# Filter.net
KiCad netlist of a schematic drawn in Altium Designer
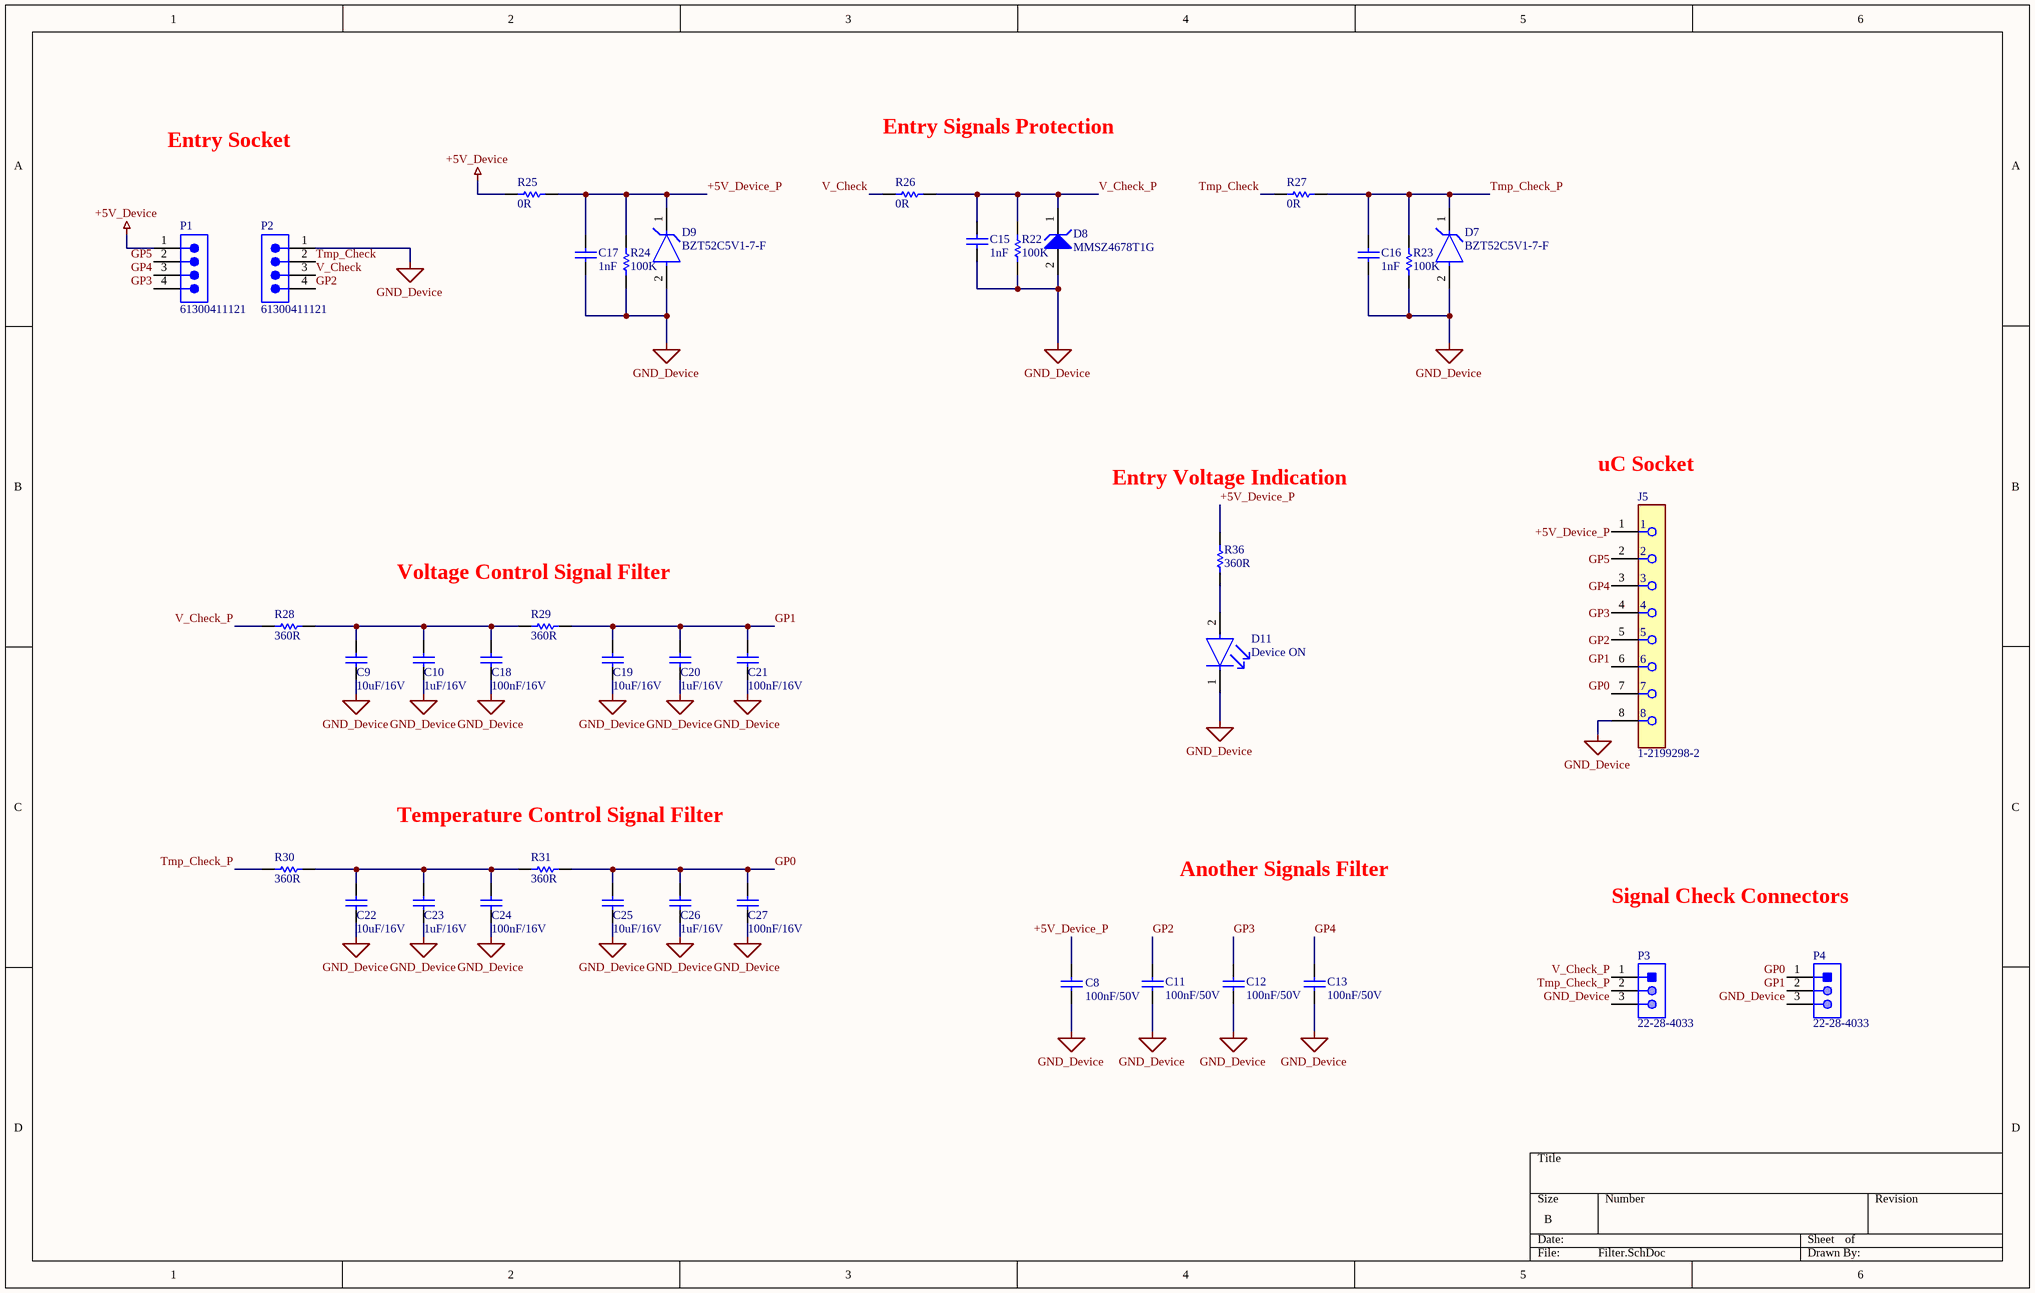
[diagram p0: Filter.SchDoc]

(export (version "E")
  (design (tool "Eeschema 10.0.6"))
  (components
    (comp (ref "C8")
      (value "100nF/50V")
      (footprint "CAPC2013X145X48NL20T23")
      (fields (field (name "MANUFACTURER") "Vitramon") (field (name "PART NUMBER") "VJ0805Y104KNAAT"))
      (libsource (lib "Altium Content Vault") (part "CAP"))
    )
    (comp (ref "C9")
      (value "10uF/16V")
      (footprint "CAPC2013X145X48NL20T23")
      (fields (field (name "MANUFACTURER") "Vitramon") (field (name "PART NUMBER") "VJ0805Y104KNAAT"))
      (libsource (lib "Altium Content Vault") (part "CAP"))
    )
    (comp (ref "C10")
      (value "1uF/16V")
      (footprint "CAPC2013X145X48NL20T23")
      (fields (field (name "MANUFACTURER") "Vitramon") (field (name "PART NUMBER") "VJ0805Y104KNAAT"))
      (libsource (lib "Altium Content Vault") (part "CAP"))
    )
    (comp (ref "C11")
      (value "100nF/50V")
      (footprint "CAPC2013X145X48NL20T23")
      (fields (field (name "MANUFACTURER") "Vitramon") (field (name "PART NUMBER") "VJ0805Y104KNAAT"))
      (libsource (lib "Altium Content Vault") (part "CAP"))
    )
    (comp (ref "C12")
      (value "100nF/50V")
      (footprint "CAPC2013X145X48NL20T23")
      (fields (field (name "MANUFACTURER") "Vitramon") (field (name "PART NUMBER") "VJ0805Y104KNAAT"))
      (libsource (lib "Altium Content Vault") (part "CAP"))
    )
    (comp (ref "C13")
      (value "100nF/50V")
      (footprint "CAPC2013X145X48NL20T23")
      (fields (field (name "MANUFACTURER") "Vitramon") (field (name "PART NUMBER") "VJ0805Y104KNAAT"))
      (libsource (lib "Altium Content Vault") (part "CAP"))
    )
    (comp (ref "C15")
      (value "1nF")
      (footprint "CAPC2013X145X48ML20T23")
      (fields (field (name "PART NUMBER") "VJ0805Y102KXAMC") (field (name "MANUFACTURER") "Vitramon"))
      (libsource (lib "Altium Content Vault") (part "CAP"))
    )
    (comp (ref "C16")
      (value "1nF")
      (footprint "CAPC2013X145X48ML20T23")
      (fields (field (name "PART NUMBER") "VJ0805Y102KXAMC") (field (name "MANUFACTURER") "Vitramon"))
      (libsource (lib "Altium Content Vault") (part "CAP"))
    )
    (comp (ref "C17")
      (value "1nF")
      (footprint "CAPC2013X145X48ML20T23")
      (fields (field (name "PART NUMBER") "VJ0805Y102KXAMC") (field (name "MANUFACTURER") "Vitramon"))
      (libsource (lib "Altium Content Vault") (part "CAP"))
    )
    (comp (ref "C18")
      (value "100nF/16V")
      (footprint "CAPC2013X145X48NL20T23")
      (fields (field (name "MANUFACTURER") "Vitramon") (field (name "PART NUMBER") "VJ0805Y104KNAAT"))
      (libsource (lib "Altium Content Vault") (part "CAP"))
    )
    (comp (ref "C19")
      (value "10uF/16V")
      (footprint "CAPC2013X145X48NL20T23")
      (fields (field (name "MANUFACTURER") "Vitramon") (field (name "PART NUMBER") "VJ0805Y104KNAAT"))
      (libsource (lib "Altium Content Vault") (part "CAP"))
    )
    (comp (ref "C20")
      (value "1uF/16V")
      (footprint "CAPC2013X145X48NL20T23")
      (fields (field (name "MANUFACTURER") "Vitramon") (field (name "PART NUMBER") "VJ0805Y104KNAAT"))
      (libsource (lib "Altium Content Vault") (part "CAP"))
    )
    (comp (ref "C21")
      (value "100nF/16V")
      (footprint "CAPC2013X145X48NL20T23")
      (fields (field (name "MANUFACTURER") "Vitramon") (field (name "PART NUMBER") "VJ0805Y104KNAAT"))
      (libsource (lib "Altium Content Vault") (part "CAP"))
    )
    (comp (ref "C22")
      (value "10uF/16V")
      (footprint "CAPC2013X145X48NL20T23")
      (fields (field (name "MANUFACTURER") "Vitramon") (field (name "PART NUMBER") "VJ0805Y104KNAAT"))
      (libsource (lib "Altium Content Vault") (part "CAP"))
    )
    (comp (ref "C23")
      (value "1uF/16V")
      (footprint "CAPC2013X145X48NL20T23")
      (fields (field (name "MANUFACTURER") "Vitramon") (field (name "PART NUMBER") "VJ0805Y104KNAAT"))
      (libsource (lib "Altium Content Vault") (part "CAP"))
    )
    (comp (ref "C24")
      (value "100nF/16V")
      (footprint "CAPC2013X145X48NL20T23")
      (fields (field (name "MANUFACTURER") "Vitramon") (field (name "PART NUMBER") "VJ0805Y104KNAAT"))
      (libsource (lib "Altium Content Vault") (part "CAP"))
    )
    (comp (ref "C25")
      (value "10uF/16V")
      (footprint "CAPC2013X145X48NL20T23")
      (fields (field (name "MANUFACTURER") "Vitramon") (field (name "PART NUMBER") "VJ0805Y104KNAAT"))
      (libsource (lib "Altium Content Vault") (part "CAP"))
    )
    (comp (ref "C26")
      (value "1uF/16V")
      (footprint "CAPC2013X145X48NL20T23")
      (fields (field (name "MANUFACTURER") "Vitramon") (field (name "PART NUMBER") "VJ0805Y104KNAAT"))
      (libsource (lib "Altium Content Vault") (part "CAP"))
    )
    (comp (ref "C27")
      (value "100nF/16V")
      (footprint "CAPC2013X145X48NL20T23")
      (fields (field (name "MANUFACTURER") "Vitramon") (field (name "PART NUMBER") "VJ0805Y104KNAAT"))
      (libsource (lib "Altium Content Vault") (part "CAP"))
    )
    (comp (ref "D7")
      (value "BZT52C5V1-7-F")
      (footprint "FP-SOD123-MFG")
      (description "DIODE ZENER 5.1V 500MW SOD123")
      (fields
        (field (name "OCTOPART") "https://octopart.com/bzt52c5v1-7-f-diodes+inc.-326718")
        (field (name "MANUFACTURER") "Diodes Incorporated")
      )
      (libsource (lib "Altium Content Vault") (part "f813f71cba58e380607f5dd3caf9714"))
    )
    (comp (ref "D8")
      (value "MMSZ4678T1G")
      (footprint "ONSC-SOD-123-2-425-04_V")
      (description "Zener Voltage Regulator, 500 mW, 2-Pin SOD-123, Pb-Free, Tape and Reel")
      (fields (field (name "MANUFACTURER") "On Semiconductor"))
      (libsource (lib "Altium Content Vault") (part "ONSC-K1A2-2"))
    )
    (comp (ref "D9")
      (value "BZT52C5V1-7-F")
      (footprint "FP-SOD123-MFG")
      (description "DIODE ZENER 5.1V 500MW SOD123")
      (fields
        (field (name "OCTOPART") "https://octopart.com/bzt52c5v1-7-f-diodes+inc.-326718")
        (field (name "MANUFACTURER") "Diodes Incorporated")
      )
      (libsource (lib "Altium Content Vault") (part "f813f71cba58e380607f5dd3caf9714"))
    )
    (comp (ref "D11")
      (value "Device ON")
      (footprint "FP-LS_R976-MFG")
      (description "LED RED DIFFUSED 0805 SMD")
      (libsource (lib "Altium Content Vault") (part "8706943c75ba83719d021d2fdc84c58"))
    )
    (comp (ref "J5")
      (value "1-2199298-2")
      (footprint "FP-1-2199298-2-MFG")
      (description "CONN IC DIP SOCKET 8POS TIN")
      (libsource (lib "Altium Content Vault") (part "b0a0b555dd3abf3683e7c330df25cc4"))
    )
    (comp (ref "P1")
      (value "61300411121")
      (footprint "61300411121")
      (libsource (lib "Altium Content Vault") (part "Header_Male_1R_04P"))
    )
    (comp (ref "P2")
      (value "61300411121")
      (footprint "61300411121")
      (libsource (lib "Altium Content Vault") (part "Header_Male_1R_04P"))
    )
    (comp (ref "P3")
      (value "22-28-4033")
      (footprint "MOLX-22-28-4033_V")
      (description "Male Header, Pitch 2.54 mm, 1 x 3 Position, Height 8.38 mm, Tail Length 3.18 mm, RoHS, Bulk")
      (fields (field (name "MANUFACTURER") "Molex"))
      (libsource (lib "Altium Content Vault") (part "CN-1P-M-R3"))
    )
    (comp (ref "P4")
      (value "22-28-4033")
      (footprint "MOLX-22-28-4033_V")
      (description "Male Header, Pitch 2.54 mm, 1 x 3 Position, Height 8.38 mm, Tail Length 3.18 mm, RoHS, Bulk")
      (fields (field (name "MANUFACTURER") "Molex"))
      (libsource (lib "Altium Content Vault") (part "CN-1P-M-R3"))
    )
    (comp (ref "R22")
      (value "100K")
      (footprint "RESC2013X55X40NL15T20")
      (fields (field (name "MANUFACTURER") "Vishay Dale") (field (name "PART NUMBER") "TNPW08052K00BEEN"))
      (libsource (lib "Altium Content Vault") (part "RES"))
    )
    (comp (ref "R23")
      (value "100K")
      (footprint "RESC2013X55X40NL15T20")
      (fields (field (name "MANUFACTURER") "Vishay Dale") (field (name "PART NUMBER") "TNPW08052K00BEEN"))
      (libsource (lib "Altium Content Vault") (part "RES"))
    )
    (comp (ref "R24")
      (value "100K")
      (footprint "RESC2013X55X40NL15T20")
      (fields (field (name "MANUFACTURER") "Vishay Dale") (field (name "PART NUMBER") "TNPW08052K00BEEN"))
      (libsource (lib "Altium Content Vault") (part "RES"))
    )
    (comp (ref "R25")
      (value "0R")
      (footprint "RESC2013X55X40NL15T20")
      (fields (field (name "MANUFACTURER") "Vishay Dale") (field (name "PART NUMBER") "TNPW08052K00BEEN"))
      (libsource (lib "Altium Content Vault") (part "RES"))
    )
    (comp (ref "R26")
      (value "0R")
      (footprint "RESC2013X55X40NL15T20")
      (fields (field (name "MANUFACTURER") "Vishay Dale") (field (name "PART NUMBER") "TNPW08052K00BEEN"))
      (libsource (lib "Altium Content Vault") (part "RES"))
    )
    (comp (ref "R27")
      (value "0R")
      (footprint "RESC2013X55X40NL15T20")
      (fields (field (name "MANUFACTURER") "Vishay Dale") (field (name "PART NUMBER") "TNPW08052K00BEEN"))
      (libsource (lib "Altium Content Vault") (part "RES"))
    )
    (comp (ref "R28")
      (value "360R")
      (footprint "RESC2013X55X40NL15T20")
      (fields (field (name "MANUFACTURER") "Vishay Dale") (field (name "PART NUMBER") "TNPW08052K00BEEN"))
      (libsource (lib "Altium Content Vault") (part "RES"))
    )
    (comp (ref "R29")
      (value "360R")
      (footprint "RESC2013X55X40NL15T20")
      (fields (field (name "MANUFACTURER") "Vishay Dale") (field (name "PART NUMBER") "TNPW08052K00BEEN"))
      (libsource (lib "Altium Content Vault") (part "RES"))
    )
    (comp (ref "R30")
      (value "360R")
      (footprint "RESC2013X55X40NL15T20")
      (fields (field (name "MANUFACTURER") "Vishay Dale") (field (name "PART NUMBER") "TNPW08052K00BEEN"))
      (libsource (lib "Altium Content Vault") (part "RES"))
    )
    (comp (ref "R31")
      (value "360R")
      (footprint "RESC2013X55X40NL15T20")
      (fields (field (name "MANUFACTURER") "Vishay Dale") (field (name "PART NUMBER") "TNPW08052K00BEEN"))
      (libsource (lib "Altium Content Vault") (part "RES"))
    )
    (comp (ref "R36")
      (value "360R")
      (footprint "RESC2013X55X40NL15T20")
      (fields (field (name "MANUFACTURER") "Vishay Dale") (field (name "PART NUMBER") "TNPW08052K00BEEN"))
      (libsource (lib "Altium Content Vault") (part "RES"))
    )
  )
  (nets
    (net (code "1") (name "+5V_Device") (class "Default")
      (node (ref "P1") (pin "1") (pinfunction "1_1") (pintype "passive"))
      (node (ref "R25") (pin "2") (pinfunction "2_2") (pintype "passive"))
    )
    (net (code "2") (name "/+5V_Device_P") (class "Default")
      (node (ref "C17") (pin "2") (pinfunction "2_2") (pintype "passive"))
      (node (ref "C8") (pin "2") (pinfunction "2_2") (pintype "passive"))
      (node (ref "D9") (pin "1") (pinfunction "C_1") (pintype "passive"))
      (node (ref "J5") (pin "1") (pinfunction "1_1") (pintype "passive"))
      (node (ref "R24") (pin "2") (pinfunction "2_2") (pintype "passive"))
      (node (ref "R25") (pin "1") (pinfunction "1_1") (pintype "passive"))
      (node (ref "R36") (pin "2") (pinfunction "2_2") (pintype "passive"))
    )
    (net (code "3") (name "/GP0") (class "Default")
      (node (ref "C25") (pin "2") (pinfunction "2_2") (pintype "passive"))
      (node (ref "C26") (pin "2") (pinfunction "2_2") (pintype "passive"))
      (node (ref "C27") (pin "2") (pinfunction "2_2") (pintype "passive"))
      (node (ref "J5") (pin "7") (pinfunction "7_7") (pintype "passive"))
      (node (ref "P4") (pin "1") (pinfunction "1_1") (pintype "passive"))
      (node (ref "R31") (pin "1") (pinfunction "1_1") (pintype "passive"))
    )
    (net (code "4") (name "/GP1") (class "Default")
      (node (ref "C19") (pin "2") (pinfunction "2_2") (pintype "passive"))
      (node (ref "C20") (pin "2") (pinfunction "2_2") (pintype "passive"))
      (node (ref "C21") (pin "2") (pinfunction "2_2") (pintype "passive"))
      (node (ref "J5") (pin "6") (pinfunction "6_6") (pintype "passive"))
      (node (ref "P4") (pin "2") (pinfunction "2_2") (pintype "passive"))
      (node (ref "R29") (pin "1") (pinfunction "1_1") (pintype "passive"))
    )
    (net (code "5") (name "/GP2") (class "Default")
      (node (ref "C11") (pin "1") (pinfunction "1_1") (pintype "passive"))
      (node (ref "J5") (pin "5") (pinfunction "5_5") (pintype "passive"))
      (node (ref "P2") (pin "4") (pinfunction "4_4") (pintype "passive"))
    )
    (net (code "6") (name "/GP3") (class "Default")
      (node (ref "C12") (pin "1") (pinfunction "1_1") (pintype "passive"))
      (node (ref "J5") (pin "4") (pinfunction "4_4") (pintype "passive"))
      (node (ref "P1") (pin "4") (pinfunction "4_4") (pintype "passive"))
    )
    (net (code "7") (name "/GP4") (class "Default")
      (node (ref "C13") (pin "1") (pinfunction "1_1") (pintype "passive"))
      (node (ref "J5") (pin "3") (pinfunction "3_3") (pintype "passive"))
      (node (ref "P1") (pin "3") (pinfunction "3_3") (pintype "passive"))
    )
    (net (code "8") (name "/GP5") (class "Default")
      (node (ref "J5") (pin "2") (pinfunction "2_2") (pintype "passive"))
      (node (ref "P1") (pin "2") (pinfunction "2_2") (pintype "passive"))
    )
    (net (code "9") (name "/Tmp_Check") (class "Default")
      (node (ref "P2") (pin "2") (pinfunction "2_2") (pintype "passive"))
      (node (ref "R27") (pin "2") (pinfunction "2_2") (pintype "passive"))
    )
    (net (code "10") (name "/Tmp_Check_P") (class "Default")
      (node (ref "C16") (pin "2") (pinfunction "2_2") (pintype "passive"))
      (node (ref "D7") (pin "1") (pinfunction "C_1") (pintype "passive"))
      (node (ref "P3") (pin "2") (pinfunction "2_2") (pintype "passive"))
      (node (ref "R23") (pin "2") (pinfunction "2_2") (pintype "passive"))
      (node (ref "R27") (pin "1") (pinfunction "1_1") (pintype "passive"))
      (node (ref "R30") (pin "2") (pinfunction "2_2") (pintype "passive"))
    )
    (net (code "11") (name "/V_Check") (class "Default")
      (node (ref "P2") (pin "3") (pinfunction "3_3") (pintype "passive"))
      (node (ref "R26") (pin "2") (pinfunction "2_2") (pintype "passive"))
    )
    (net (code "12") (name "/V_Check_P") (class "Default")
      (node (ref "C15") (pin "2") (pinfunction "2_2") (pintype "passive"))
      (node (ref "D8") (pin "1") (pinfunction "K_1") (pintype "passive"))
      (node (ref "P3") (pin "1") (pinfunction "1_1") (pintype "passive"))
      (node (ref "R22") (pin "2") (pinfunction "2_2") (pintype "passive"))
      (node (ref "R26") (pin "1") (pinfunction "1_1") (pintype "passive"))
      (node (ref "R28") (pin "2") (pinfunction "2_2") (pintype "passive"))
    )
    (net (code "13") (name "GND_Device") (class "Default")
      (node (ref "C10") (pin "1") (pinfunction "1_1") (pintype "passive"))
      (node (ref "C11") (pin "2") (pinfunction "2_2") (pintype "passive"))
      (node (ref "C12") (pin "2") (pinfunction "2_2") (pintype "passive"))
      (node (ref "C13") (pin "2") (pinfunction "2_2") (pintype "passive"))
      (node (ref "C15") (pin "1") (pinfunction "1_1") (pintype "passive"))
      (node (ref "C16") (pin "1") (pinfunction "1_1") (pintype "passive"))
      (node (ref "C17") (pin "1") (pinfunction "1_1") (pintype "passive"))
      (node (ref "C18") (pin "1") (pinfunction "1_1") (pintype "passive"))
      (node (ref "C19") (pin "1") (pinfunction "1_1") (pintype "passive"))
      (node (ref "C20") (pin "1") (pinfunction "1_1") (pintype "passive"))
      (node (ref "C21") (pin "1") (pinfunction "1_1") (pintype "passive"))
      (node (ref "C22") (pin "1") (pinfunction "1_1") (pintype "passive"))
      (node (ref "C23") (pin "1") (pinfunction "1_1") (pintype "passive"))
      (node (ref "C24") (pin "1") (pinfunction "1_1") (pintype "passive"))
      (node (ref "C25") (pin "1") (pinfunction "1_1") (pintype "passive"))
      (node (ref "C26") (pin "1") (pinfunction "1_1") (pintype "passive"))
      (node (ref "C27") (pin "1") (pinfunction "1_1") (pintype "passive"))
      (node (ref "C8") (pin "1") (pinfunction "1_1") (pintype "passive"))
      (node (ref "C9") (pin "1") (pinfunction "1_1") (pintype "passive"))
      (node (ref "D11") (pin "1") (pinfunction "C_1") (pintype "passive"))
      (node (ref "D7") (pin "2") (pinfunction "A_2") (pintype "passive"))
      (node (ref "D8") (pin "2") (pinfunction "A_2") (pintype "passive"))
      (node (ref "D9") (pin "2") (pinfunction "A_2") (pintype "passive"))
      (node (ref "J5") (pin "8") (pinfunction "8_8") (pintype "passive"))
      (node (ref "P2") (pin "1") (pinfunction "1_1") (pintype "passive"))
      (node (ref "P3") (pin "3") (pinfunction "3_3") (pintype "passive"))
      (node (ref "P4") (pin "3") (pinfunction "3_3") (pintype "passive"))
      (node (ref "R22") (pin "1") (pinfunction "1_1") (pintype "passive"))
      (node (ref "R23") (pin "1") (pinfunction "1_1") (pintype "passive"))
      (node (ref "R24") (pin "1") (pinfunction "1_1") (pintype "passive"))
    )
    (net (code "14") (name "Net-(C10-Pad2)") (class "Default")
      (node (ref "C10") (pin "2") (pinfunction "2_2") (pintype "passive"))
      (node (ref "C18") (pin "2") (pinfunction "2_2") (pintype "passive"))
      (node (ref "C9") (pin "2") (pinfunction "2_2") (pintype "passive"))
      (node (ref "R28") (pin "1") (pinfunction "1_1") (pintype "passive"))
      (node (ref "R29") (pin "2") (pinfunction "2_2") (pintype "passive"))
    )
    (net (code "15") (name "Net-(C22-Pad2)") (class "Default")
      (node (ref "C22") (pin "2") (pinfunction "2_2") (pintype "passive"))
      (node (ref "C23") (pin "2") (pinfunction "2_2") (pintype "passive"))
      (node (ref "C24") (pin "2") (pinfunction "2_2") (pintype "passive"))
      (node (ref "R30") (pin "1") (pinfunction "1_1") (pintype "passive"))
      (node (ref "R31") (pin "2") (pinfunction "2_2") (pintype "passive"))
    )
    (net (code "16") (name "Net-(D11-A)") (class "Default")
      (node (ref "D11") (pin "2") (pinfunction "A_2") (pintype "passive"))
      (node (ref "R36") (pin "1") (pinfunction "1_1") (pintype "passive"))
    )
  )
)
